# logique.net
KiCad netlist of a schematic drawn in Altium Designer
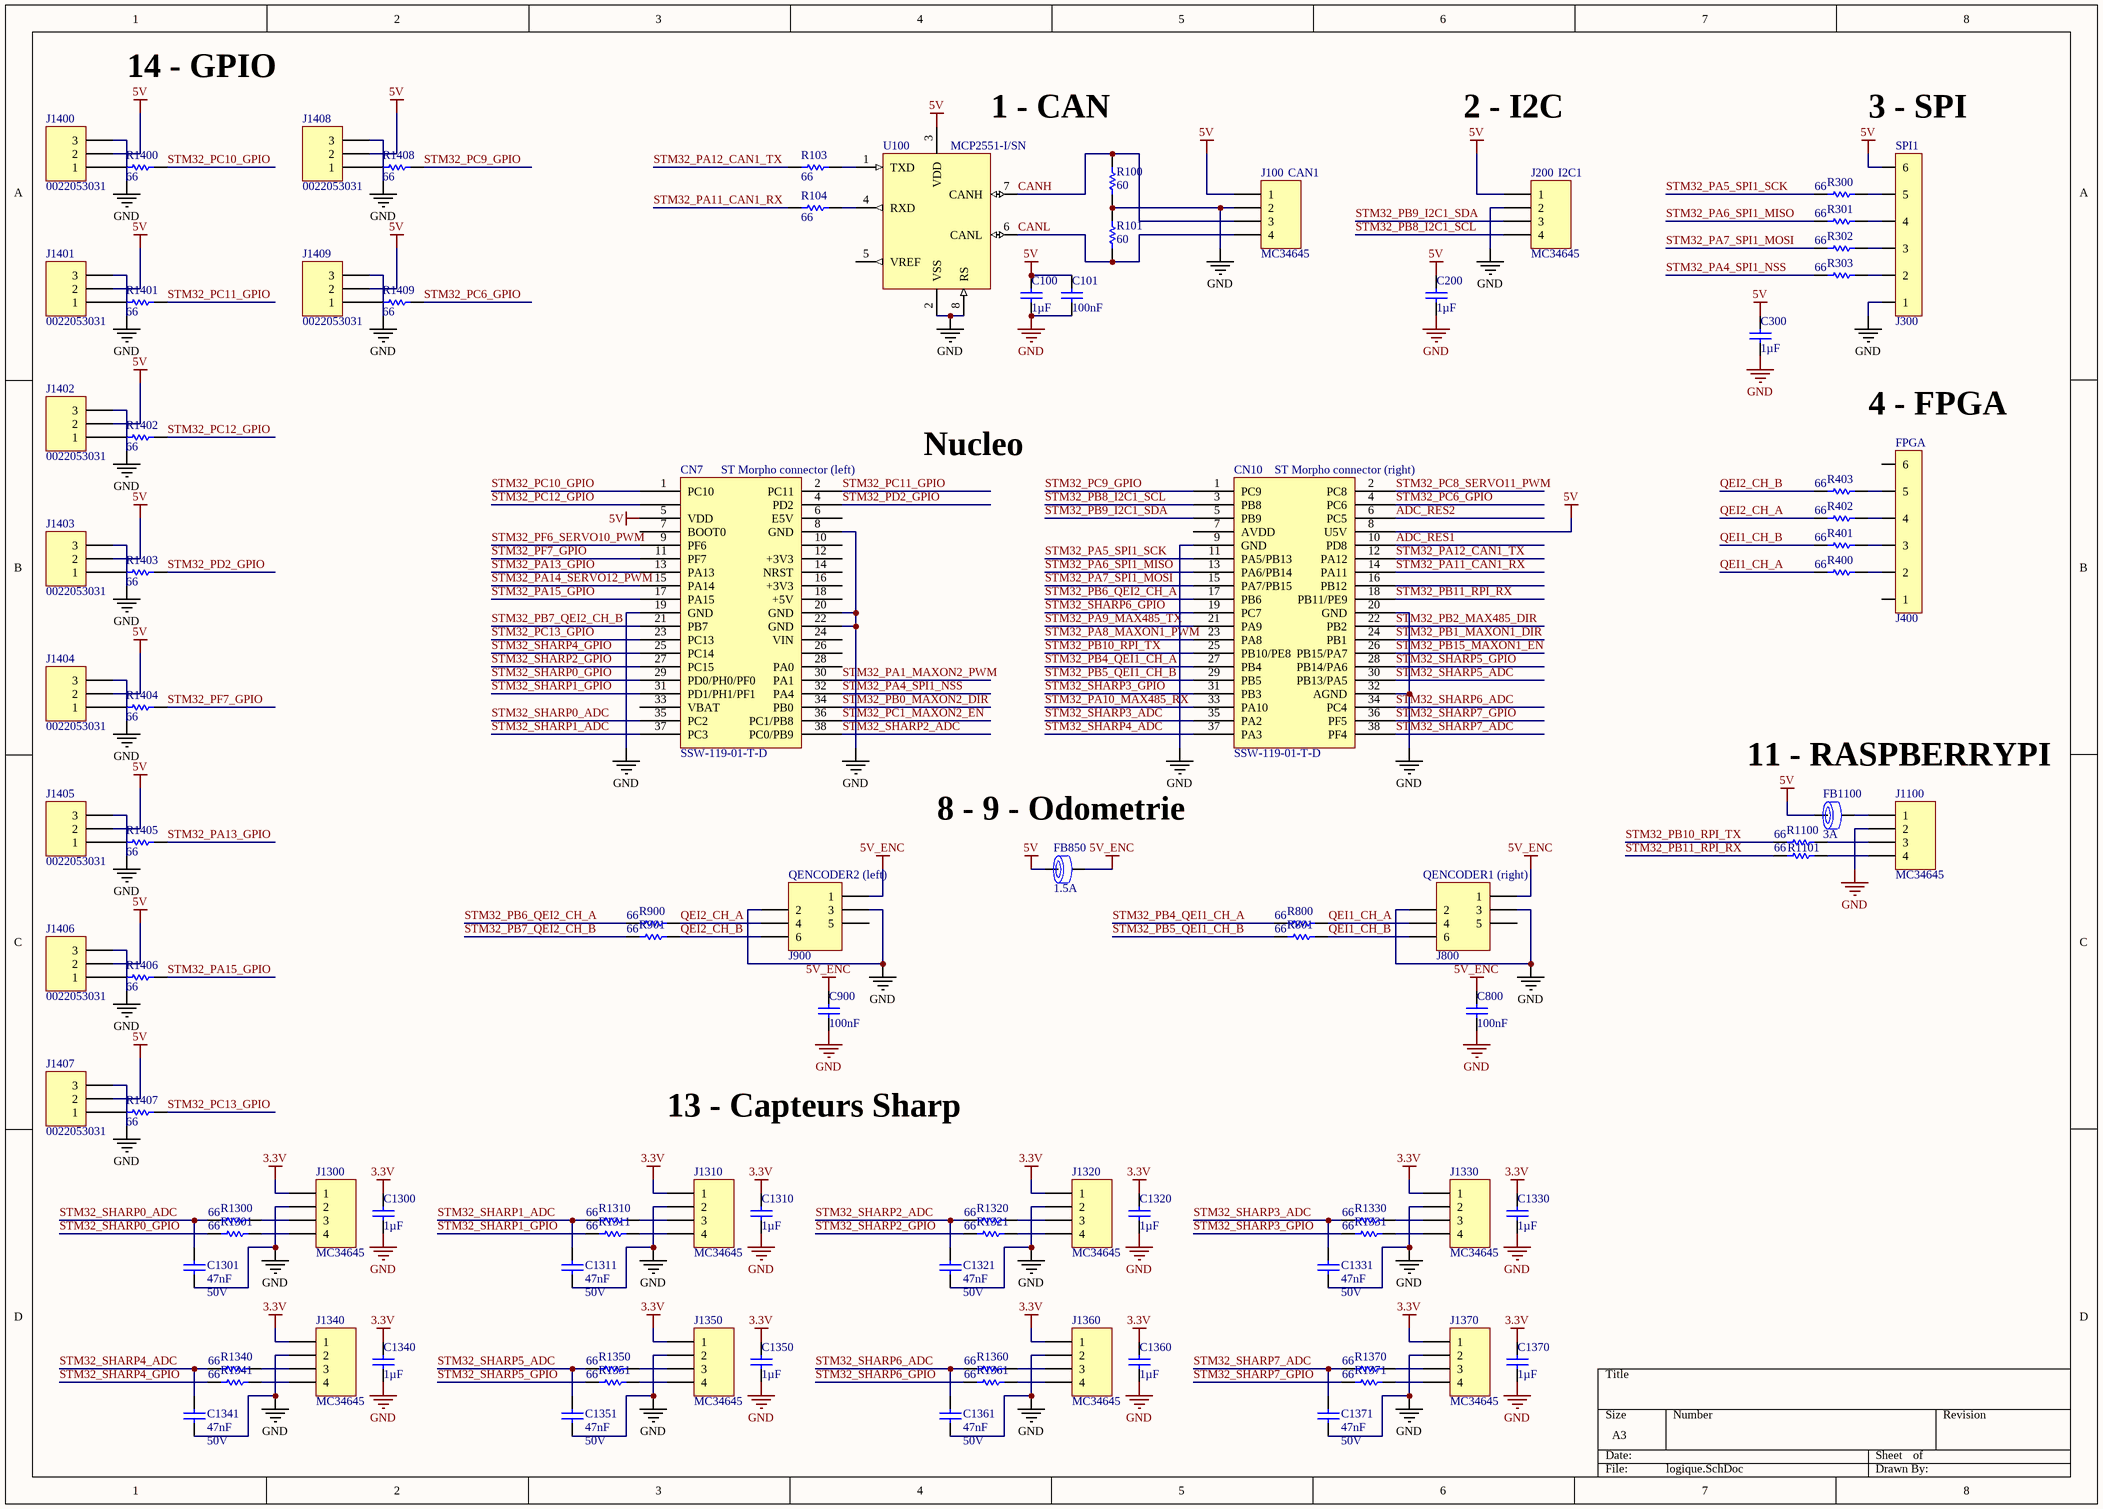
[diagram p0: logique.SchDoc]

(export (version "E")
  (design (tool "Eeschema 10.0.6"))
  (components
    (comp (ref "C100")
      (value "1µF")
      (footprint "C0805_N")
      (description "Capacitor")
      (fields (field (name "PUBLISHER") "Altium Limited"))
      (libsource (lib "_ROBOT") (part "Condensateur"))
    )
    (comp (ref "C101")
      (value "100nF")
      (footprint "C0805_N")
      (description "Capacitor")
      (fields (field (name "PUBLISHER") "Altium Limited"))
      (libsource (lib "_ROBOT") (part "Condensateur"))
    )
    (comp (ref "C200")
      (value "1µF")
      (footprint "C0805_N")
      (description "Capacitor")
      (fields (field (name "PUBLISHER") "Altium Limited"))
      (libsource (lib "_ROBOT") (part "Condensateur"))
    )
    (comp (ref "C300")
      (value "1µF")
      (footprint "C0805_N")
      (description "Capacitor")
      (fields (field (name "PUBLISHER") "Altium Limited"))
      (libsource (lib "_ROBOT") (part "Condensateur"))
    )
    (comp (ref "C800")
      (value "100nF")
      (footprint "C0805_N")
      (description "Capacitor")
      (fields (field (name "PUBLISHER") "Altium Limited"))
      (libsource (lib "_ROBOT") (part "Condensateur"))
    )
    (comp (ref "C900")
      (value "100nF")
      (footprint "C0805_N")
      (description "Capacitor")
      (fields (field (name "PUBLISHER") "Altium Limited"))
      (libsource (lib "_ROBOT") (part "Condensateur"))
    )
    (comp (ref "C1300")
      (value "1µF")
      (footprint "C0805_N")
      (description "Capacitor")
      (fields (field (name "PUBLISHER") "Altium Limited"))
      (libsource (lib "_ROBOT") (part "Condensateur"))
    )
    (comp (ref "C1301")
      (value "47nF")
      (footprint "WCAP-CSGP_0603, 1.6x0.8x0.8")
      (description "CAP CER 47nF 50V X7R 0603")
      (fields
        (field (name "MANUFACTURER") "Wurth Elektronik")
        (field (name "MANUFACTURER PART NUMBER") "885012206093")
        (field (name "RATEDVOLTAGE") "50V")
      )
      (libsource (lib "Condensateur") (part "WCAP-CSGP, 885012206093"))
    )
    (comp (ref "C1310")
      (value "1µF")
      (footprint "C0805_N")
      (description "Capacitor")
      (fields (field (name "PUBLISHER") "Altium Limited"))
      (libsource (lib "_ROBOT") (part "Condensateur"))
    )
    (comp (ref "C1311")
      (value "47nF")
      (footprint "WCAP-CSGP_0603, 1.6x0.8x0.8")
      (description "CAP CER 47nF 50V X7R 0603")
      (fields
        (field (name "MANUFACTURER") "Wurth Elektronik")
        (field (name "MANUFACTURER PART NUMBER") "885012206093")
        (field (name "RATEDVOLTAGE") "50V")
      )
      (libsource (lib "Condensateur") (part "WCAP-CSGP, 885012206093"))
    )
    (comp (ref "C1320")
      (value "1µF")
      (footprint "C0805_N")
      (description "Capacitor")
      (fields (field (name "PUBLISHER") "Altium Limited"))
      (libsource (lib "_ROBOT") (part "Condensateur"))
    )
    (comp (ref "C1321")
      (value "47nF")
      (footprint "WCAP-CSGP_0603, 1.6x0.8x0.8")
      (description "CAP CER 47nF 50V X7R 0603")
      (fields
        (field (name "MANUFACTURER") "Wurth Elektronik")
        (field (name "MANUFACTURER PART NUMBER") "885012206093")
        (field (name "RATEDVOLTAGE") "50V")
      )
      (libsource (lib "Condensateur") (part "WCAP-CSGP, 885012206093"))
    )
    (comp (ref "C1330")
      (value "1µF")
      (footprint "C0805_N")
      (description "Capacitor")
      (fields (field (name "PUBLISHER") "Altium Limited"))
      (libsource (lib "_ROBOT") (part "Condensateur"))
    )
    (comp (ref "C1331")
      (value "47nF")
      (footprint "WCAP-CSGP_0603, 1.6x0.8x0.8")
      (description "CAP CER 47nF 50V X7R 0603")
      (fields
        (field (name "MANUFACTURER") "Wurth Elektronik")
        (field (name "MANUFACTURER PART NUMBER") "885012206093")
        (field (name "RATEDVOLTAGE") "50V")
      )
      (libsource (lib "Condensateur") (part "WCAP-CSGP, 885012206093"))
    )
    (comp (ref "C1340")
      (value "1µF")
      (footprint "C0805_N")
      (description "Capacitor")
      (fields (field (name "PUBLISHER") "Altium Limited"))
      (libsource (lib "_ROBOT") (part "Condensateur"))
    )
    (comp (ref "C1341")
      (value "47nF")
      (footprint "WCAP-CSGP_0603, 1.6x0.8x0.8")
      (description "CAP CER 47nF 50V X7R 0603")
      (fields
        (field (name "MANUFACTURER") "Wurth Elektronik")
        (field (name "MANUFACTURER PART NUMBER") "885012206093")
        (field (name "RATEDVOLTAGE") "50V")
      )
      (libsource (lib "Condensateur") (part "WCAP-CSGP, 885012206093"))
    )
    (comp (ref "C1350")
      (value "1µF")
      (footprint "C0805_N")
      (description "Capacitor")
      (fields (field (name "PUBLISHER") "Altium Limited"))
      (libsource (lib "_ROBOT") (part "Condensateur"))
    )
    (comp (ref "C1351")
      (value "47nF")
      (footprint "WCAP-CSGP_0603, 1.6x0.8x0.8")
      (description "CAP CER 47nF 50V X7R 0603")
      (fields
        (field (name "MANUFACTURER") "Wurth Elektronik")
        (field (name "MANUFACTURER PART NUMBER") "885012206093")
        (field (name "RATEDVOLTAGE") "50V")
      )
      (libsource (lib "Condensateur") (part "WCAP-CSGP, 885012206093"))
    )
    (comp (ref "C1360")
      (value "1µF")
      (footprint "C0805_N")
      (description "Capacitor")
      (fields (field (name "PUBLISHER") "Altium Limited"))
      (libsource (lib "_ROBOT") (part "Condensateur"))
    )
    (comp (ref "C1361")
      (value "47nF")
      (footprint "WCAP-CSGP_0603, 1.6x0.8x0.8")
      (description "CAP CER 47nF 50V X7R 0603")
      (fields
        (field (name "MANUFACTURER") "Wurth Elektronik")
        (field (name "MANUFACTURER PART NUMBER") "885012206093")
        (field (name "RATEDVOLTAGE") "50V")
      )
      (libsource (lib "Condensateur") (part "WCAP-CSGP, 885012206093"))
    )
    (comp (ref "C1370")
      (value "1µF")
      (footprint "C0805_N")
      (description "Capacitor")
      (fields (field (name "PUBLISHER") "Altium Limited"))
      (libsource (lib "_ROBOT") (part "Condensateur"))
    )
    (comp (ref "C1371")
      (value "47nF")
      (footprint "WCAP-CSGP_0603, 1.6x0.8x0.8")
      (description "CAP CER 47nF 50V X7R 0603")
      (fields
        (field (name "MANUFACTURER") "Wurth Elektronik")
        (field (name "MANUFACTURER PART NUMBER") "885012206093")
        (field (name "RATEDVOLTAGE") "50V")
      )
      (libsource (lib "Condensateur") (part "WCAP-CSGP, 885012206093"))
    )
    (comp (ref "CN7")
      (value "SSW-119-01-T-D")
      (footprint "Samtec:CONN RCPT .100\" 38POS DUAL TIN")
      (description "CONN RCPT .100\" 38POS DUAL TIN")
      (fields (field (name "MANUFACTURER") "Samtec Inc."))
      (libsource (lib "Samtec") (part "SSW-119-01-T-D"))
    )
    (comp (ref "CN10")
      (value "SSW-119-01-T-D")
      (footprint "Samtec:CONN RCPT .100\" 38POS DUAL TIN")
      (description "CONN RCPT .100\" 38POS DUAL TIN")
      (fields (field (name "MANUFACTURER") "Samtec Inc."))
      (libsource (lib "Samtec") (part "SSW-119-01-T-D"))
    )
    (comp (ref "FB850")
      (value "742792624")
      (footprint "WE-CBF_0603_High Current")
      (description "Ferrite Bead 180ohm 0603 max1.5A")
      (fields (field (name "MANUFACTURER") "Wurth Elektronik") (field (name "RATEDCURRENT") "1.5A"))
      (libsource (lib "Inductance") (part "WE-CBF, 742792624"))
    )
    (comp (ref "FB1100")
      (value "742792023")
      (footprint "WE-CBF_0805_High Current")
      (description "Ferrite Bead 120ohm 0805 max3.0A")
      (fields (field (name "MANUFACTURER") "Wurth Elektronik") (field (name "RATEDCURRENT") "3A"))
      (libsource (lib "Inductance") (part "WE-CBF, 742792023"))
    )
    (comp (ref "J100")
      (value "MC34645")
      (footprint "HDR1X4")
      (description "MULTICOMP - MC34645 - EMB. MALE COUDEE  CON. MALE 2.54MM 4VOIE")
      (fields (field (name "MANUFACTURER") "MULTICOMP"))
      (libsource (lib "Divers") (part "MC34645"))
    )
    (comp (ref "J200")
      (value "MC34645")
      (footprint "HDR1X4")
      (description "MULTICOMP - MC34645 - EMB. MALE COUDEE  CON. MALE 2.54MM 4VOIE")
      (fields (field (name "MANUFACTURER") "MULTICOMP"))
      (libsource (lib "Divers") (part "MC34645"))
    )
    (comp (ref "J300")
      (value "22-03-2061")
      (footprint "22-03-2061")
      (libsource (lib "Connecteurs") (part "22-03-2061"))
    )
    (comp (ref "J400")
      (value "22-03-2061")
      (footprint "22-03-2061")
      (libsource (lib "Connecteurs") (part "22-03-2061"))
    )
    (comp (ref "J800")
      (value "~")
      (footprint "690367280676")
      (description "WR-MM Female SMT Connector with Polarization")
      (fields (field (name "MANUFACTURER PART NUMBER") "690367280676"))
      (libsource (lib "Connecteurs") (part "690367280676"))
    )
    (comp (ref "J900")
      (value "~")
      (footprint "690367280676")
      (description "WR-MM Female SMT Connector with Polarization")
      (fields (field (name "MANUFACTURER PART NUMBER") "690367280676"))
      (libsource (lib "Connecteurs") (part "690367280676"))
    )
    (comp (ref "J1100")
      (value "MC34645")
      (footprint "HDR1X4")
      (description "MULTICOMP - MC34645 - EMB. MALE COUDEE  CON. MALE 2.54MM 4VOIE")
      (fields (field (name "MANUFACTURER") "MULTICOMP"))
      (libsource (lib "Divers") (part "MC34645"))
    )
    (comp (ref "J1300")
      (value "MC34645")
      (footprint "HDR1X4")
      (description "MULTICOMP - MC34645 - EMB. MALE COUDEE  CON. MALE 2.54MM 4VOIE")
      (fields (field (name "MANUFACTURER") "MULTICOMP"))
      (libsource (lib "Connecteurs") (part "MC34645"))
    )
    (comp (ref "J1310")
      (value "MC34645")
      (footprint "HDR1X4")
      (description "MULTICOMP - MC34645 - EMB. MALE COUDEE  CON. MALE 2.54MM 4VOIE")
      (fields (field (name "MANUFACTURER") "MULTICOMP"))
      (libsource (lib "Connecteurs") (part "MC34645"))
    )
    (comp (ref "J1320")
      (value "MC34645")
      (footprint "HDR1X4")
      (description "MULTICOMP - MC34645 - EMB. MALE COUDEE  CON. MALE 2.54MM 4VOIE")
      (fields (field (name "MANUFACTURER") "MULTICOMP"))
      (libsource (lib "Connecteurs") (part "MC34645"))
    )
    (comp (ref "J1330")
      (value "MC34645")
      (footprint "HDR1X4")
      (description "MULTICOMP - MC34645 - EMB. MALE COUDEE  CON. MALE 2.54MM 4VOIE")
      (fields (field (name "MANUFACTURER") "MULTICOMP"))
      (libsource (lib "Connecteurs") (part "MC34645"))
    )
    (comp (ref "J1340")
      (value "MC34645")
      (footprint "HDR1X4")
      (description "MULTICOMP - MC34645 - EMB. MALE COUDEE  CON. MALE 2.54MM 4VOIE")
      (fields (field (name "MANUFACTURER") "MULTICOMP"))
      (libsource (lib "Connecteurs") (part "MC34645"))
    )
    (comp (ref "J1350")
      (value "MC34645")
      (footprint "HDR1X4")
      (description "MULTICOMP - MC34645 - EMB. MALE COUDEE  CON. MALE 2.54MM 4VOIE")
      (fields (field (name "MANUFACTURER") "MULTICOMP"))
      (libsource (lib "Connecteurs") (part "MC34645"))
    )
    (comp (ref "J1360")
      (value "MC34645")
      (footprint "HDR1X4")
      (description "MULTICOMP - MC34645 - EMB. MALE COUDEE  CON. MALE 2.54MM 4VOIE")
      (fields (field (name "MANUFACTURER") "MULTICOMP"))
      (libsource (lib "Connecteurs") (part "MC34645"))
    )
    (comp (ref "J1370")
      (value "MC34645")
      (footprint "HDR1X4")
      (description "MULTICOMP - MC34645 - EMB. MALE COUDEE  CON. MALE 2.54MM 4VOIE")
      (fields (field (name "MANUFACTURER") "MULTICOMP"))
      (libsource (lib "Connecteurs") (part "MC34645"))
    )
    (comp (ref "J1400")
      (value "0022053031")
      (footprint "HDR1X3")
      (description "CONN HEADER 3POS .100 R/A TIN")
      (fields (field (name "MANUFACTURER") "Molex, LLC"))
      (libsource (lib "Divers") (part "0022053031"))
    )
    (comp (ref "J1401")
      (value "0022053031")
      (footprint "HDR1X3")
      (description "CONN HEADER 3POS .100 R/A TIN")
      (fields (field (name "MANUFACTURER") "Molex, LLC"))
      (libsource (lib "Divers") (part "0022053031"))
    )
    (comp (ref "J1402")
      (value "0022053031")
      (footprint "HDR1X3")
      (description "CONN HEADER 3POS .100 R/A TIN")
      (fields (field (name "MANUFACTURER") "Molex, LLC"))
      (libsource (lib "Divers") (part "0022053031"))
    )
    (comp (ref "J1403")
      (value "0022053031")
      (footprint "HDR1X3")
      (description "CONN HEADER 3POS .100 R/A TIN")
      (fields (field (name "MANUFACTURER") "Molex, LLC"))
      (libsource (lib "Divers") (part "0022053031"))
    )
    (comp (ref "J1404")
      (value "0022053031")
      (footprint "HDR1X3")
      (description "CONN HEADER 3POS .100 R/A TIN")
      (fields (field (name "MANUFACTURER") "Molex, LLC"))
      (libsource (lib "Divers") (part "0022053031"))
    )
    (comp (ref "J1405")
      (value "0022053031")
      (footprint "HDR1X3")
      (description "CONN HEADER 3POS .100 R/A TIN")
      (fields (field (name "MANUFACTURER") "Molex, LLC"))
      (libsource (lib "Divers") (part "0022053031"))
    )
    (comp (ref "J1406")
      (value "0022053031")
      (footprint "HDR1X3")
      (description "CONN HEADER 3POS .100 R/A TIN")
      (fields (field (name "MANUFACTURER") "Molex, LLC"))
      (libsource (lib "Divers") (part "0022053031"))
    )
    (comp (ref "J1407")
      (value "0022053031")
      (footprint "HDR1X3")
      (description "CONN HEADER 3POS .100 R/A TIN")
      (fields (field (name "MANUFACTURER") "Molex, LLC"))
      (libsource (lib "Divers") (part "0022053031"))
    )
    (comp (ref "J1408")
      (value "0022053031")
      (footprint "HDR1X3")
      (description "CONN HEADER 3POS .100 R/A TIN")
      (fields (field (name "MANUFACTURER") "Molex, LLC"))
      (libsource (lib "Divers") (part "0022053031"))
    )
    (comp (ref "J1409")
      (value "0022053031")
      (footprint "HDR1X3")
      (description "CONN HEADER 3POS .100 R/A TIN")
      (fields (field (name "MANUFACTURER") "Molex, LLC"))
      (libsource (lib "Divers") (part "0022053031"))
    )
    (comp (ref "R100")
      (value "60")
      (footprint "R0805_N")
      (description "Resistor")
      (fields (field (name "PUBLISHER") "Altium Limited"))
      (libsource (lib "_ROBOT") (part "Resistor"))
    )
    (comp (ref "R101")
      (value "60")
      (footprint "R0805_N")
      (description "Resistor")
      (fields (field (name "PUBLISHER") "Altium Limited"))
      (libsource (lib "_ROBOT") (part "Resistor"))
    )
    (comp (ref "R103")
      (value "66")
      (footprint "R0805_N")
      (description "Resistor")
      (fields (field (name "PUBLISHER") "Altium Limited"))
      (libsource (lib "_ROBOT") (part "Resistor"))
    )
    (comp (ref "R104")
      (value "66")
      (footprint "R0805_N")
      (description "Resistor")
      (fields (field (name "PUBLISHER") "Altium Limited"))
      (libsource (lib "_ROBOT") (part "Resistor"))
    )
    (comp (ref "R300")
      (value "66")
      (footprint "R0805_N")
      (description "Resistor")
      (fields (field (name "PUBLISHER") "Altium Limited"))
      (libsource (lib "_ROBOT") (part "Resistor"))
    )
    (comp (ref "R301")
      (value "66")
      (footprint "R0805_N")
      (description "Resistor")
      (fields (field (name "PUBLISHER") "Altium Limited"))
      (libsource (lib "_ROBOT") (part "Resistor"))
    )
    (comp (ref "R302")
      (value "66")
      (footprint "R0805_N")
      (description "Resistor")
      (fields (field (name "PUBLISHER") "Altium Limited"))
      (libsource (lib "_ROBOT") (part "Resistor"))
    )
    (comp (ref "R303")
      (value "66")
      (footprint "R0805_N")
      (description "Resistor")
      (fields (field (name "PUBLISHER") "Altium Limited"))
      (libsource (lib "_ROBOT") (part "Resistor"))
    )
    (comp (ref "R400")
      (value "66")
      (footprint "R0805_N")
      (description "Resistor")
      (fields (field (name "PUBLISHER") "Altium Limited"))
      (libsource (lib "_ROBOT") (part "Resistor"))
    )
    (comp (ref "R401")
      (value "66")
      (footprint "R0805_N")
      (description "Resistor")
      (fields (field (name "PUBLISHER") "Altium Limited"))
      (libsource (lib "_ROBOT") (part "Resistor"))
    )
    (comp (ref "R402")
      (value "66")
      (footprint "R0805_N")
      (description "Resistor")
      (fields (field (name "PUBLISHER") "Altium Limited"))
      (libsource (lib "_ROBOT") (part "Resistor"))
    )
    (comp (ref "R403")
      (value "66")
      (footprint "R0805_N")
      (description "Resistor")
      (fields (field (name "PUBLISHER") "Altium Limited"))
      (libsource (lib "_ROBOT") (part "Resistor"))
    )
    (comp (ref "R800")
      (value "66")
      (footprint "R0805_N")
      (description "Resistor")
      (fields (field (name "PUBLISHER") "Altium Limited"))
      (libsource (lib "_ROBOT") (part "Resistor"))
    )
    (comp (ref "R801")
      (value "66")
      (footprint "R0805_N")
      (description "Resistor")
      (fields (field (name "PUBLISHER") "Altium Limited"))
      (libsource (lib "_ROBOT") (part "Resistor"))
    )
    (comp (ref "R900")
      (value "66")
      (footprint "R0805_N")
      (description "Resistor")
      (fields (field (name "PUBLISHER") "Altium Limited"))
      (libsource (lib "_ROBOT") (part "Resistor"))
    )
    (comp (ref "R901")
      (value "66")
      (footprint "R0805_N")
      (description "Resistor")
      (fields (field (name "PUBLISHER") "Altium Limited"))
      (libsource (lib "_ROBOT") (part "Resistor"))
    )
    (comp (ref "R1100")
      (value "66")
      (footprint "R0805_N")
      (description "Resistor")
      (fields (field (name "PUBLISHER") "Altium Limited"))
      (libsource (lib "_ROBOT") (part "Resistor"))
    )
    (comp (ref "R1101")
      (value "66")
      (footprint "R0805_N")
      (description "Resistor")
      (fields (field (name "PUBLISHER") "Altium Limited"))
      (libsource (lib "_ROBOT") (part "Resistor"))
    )
    (comp (ref "R1300")
      (value "66")
      (footprint "R0805_N")
      (description "Resistor")
      (fields (field (name "PUBLISHER") "Altium Limited"))
      (libsource (lib "_ROBOT") (part "Resistor"))
    )
    (comp (ref "R1301")
      (value "66")
      (footprint "R0805_N")
      (description "Resistor")
      (fields (field (name "PUBLISHER") "Altium Limited"))
      (libsource (lib "_ROBOT") (part "Resistor"))
    )
    (comp (ref "R1310")
      (value "66")
      (footprint "R0805_N")
      (description "Resistor")
      (fields (field (name "PUBLISHER") "Altium Limited"))
      (libsource (lib "_ROBOT") (part "Resistor"))
    )
    (comp (ref "R1311")
      (value "66")
      (footprint "R0805_N")
      (description "Resistor")
      (fields (field (name "PUBLISHER") "Altium Limited"))
      (libsource (lib "_ROBOT") (part "Resistor"))
    )
    (comp (ref "R1320")
      (value "66")
      (footprint "R0805_N")
      (description "Resistor")
      (fields (field (name "PUBLISHER") "Altium Limited"))
      (libsource (lib "_ROBOT") (part "Resistor"))
    )
    (comp (ref "R1321")
      (value "66")
      (footprint "R0805_N")
      (description "Resistor")
      (fields (field (name "PUBLISHER") "Altium Limited"))
      (libsource (lib "_ROBOT") (part "Resistor"))
    )
    (comp (ref "R1330")
      (value "66")
      (footprint "R0805_N")
      (description "Resistor")
      (fields (field (name "PUBLISHER") "Altium Limited"))
      (libsource (lib "_ROBOT") (part "Resistor"))
    )
    (comp (ref "R1331")
      (value "66")
      (footprint "R0805_N")
      (description "Resistor")
      (fields (field (name "PUBLISHER") "Altium Limited"))
      (libsource (lib "_ROBOT") (part "Resistor"))
    )
    (comp (ref "R1340")
      (value "66")
      (footprint "R0805_N")
      (description "Resistor")
      (fields (field (name "PUBLISHER") "Altium Limited"))
      (libsource (lib "_ROBOT") (part "Resistor"))
    )
    (comp (ref "R1341")
      (value "66")
      (footprint "R0805_N")
      (description "Resistor")
      (fields (field (name "PUBLISHER") "Altium Limited"))
      (libsource (lib "_ROBOT") (part "Resistor"))
    )
    (comp (ref "R1350")
      (value "66")
      (footprint "R0805_N")
      (description "Resistor")
      (fields (field (name "PUBLISHER") "Altium Limited"))
      (libsource (lib "_ROBOT") (part "Resistor"))
    )
    (comp (ref "R1351")
      (value "66")
      (footprint "R0805_N")
      (description "Resistor")
      (fields (field (name "PUBLISHER") "Altium Limited"))
      (libsource (lib "_ROBOT") (part "Resistor"))
    )
    (comp (ref "R1360")
      (value "66")
      (footprint "R0805_N")
      (description "Resistor")
      (fields (field (name "PUBLISHER") "Altium Limited"))
      (libsource (lib "_ROBOT") (part "Resistor"))
    )
    (comp (ref "R1361")
      (value "66")
      (footprint "R0805_N")
      (description "Resistor")
      (fields (field (name "PUBLISHER") "Altium Limited"))
      (libsource (lib "_ROBOT") (part "Resistor"))
    )
    (comp (ref "R1370")
      (value "66")
      (footprint "R0805_N")
      (description "Resistor")
      (fields (field (name "PUBLISHER") "Altium Limited"))
      (libsource (lib "_ROBOT") (part "Resistor"))
    )
    (comp (ref "R1371")
      (value "66")
      (footprint "R0805_N")
      (description "Resistor")
      (fields (field (name "PUBLISHER") "Altium Limited"))
      (libsource (lib "_ROBOT") (part "Resistor"))
    )
    (comp (ref "R1400")
      (value "66")
      (footprint "R0805_N")
      (description "Resistor")
      (fields (field (name "PUBLISHER") "Altium Limited"))
      (libsource (lib "_ROBOT") (part "Resistor"))
    )
    (comp (ref "R1401")
      (value "66")
      (footprint "R0805_N")
      (description "Resistor")
      (fields (field (name "PUBLISHER") "Altium Limited"))
      (libsource (lib "_ROBOT") (part "Resistor"))
    )
    (comp (ref "R1402")
      (value "66")
      (footprint "R0805_N")
      (description "Resistor")
      (fields (field (name "PUBLISHER") "Altium Limited"))
      (libsource (lib "_ROBOT") (part "Resistor"))
    )
    (comp (ref "R1403")
      (value "66")
      (footprint "R0805_N")
      (description "Resistor")
      (fields (field (name "PUBLISHER") "Altium Limited"))
      (libsource (lib "_ROBOT") (part "Resistor"))
    )
    (comp (ref "R1404")
      (value "66")
      (footprint "R0805_N")
      (description "Resistor")
      (fields (field (name "PUBLISHER") "Altium Limited"))
      (libsource (lib "_ROBOT") (part "Resistor"))
    )
    (comp (ref "R1405")
      (value "66")
      (footprint "R0805_N")
      (description "Resistor")
      (fields (field (name "PUBLISHER") "Altium Limited"))
      (libsource (lib "_ROBOT") (part "Resistor"))
    )
    (comp (ref "R1406")
      (value "66")
      (footprint "R0805_N")
      (description "Resistor")
      (fields (field (name "PUBLISHER") "Altium Limited"))
      (libsource (lib "_ROBOT") (part "Resistor"))
    )
    (comp (ref "R1407")
      (value "66")
      (footprint "R0805_N")
      (description "Resistor")
      (fields (field (name "PUBLISHER") "Altium Limited"))
      (libsource (lib "_ROBOT") (part "Resistor"))
    )
    (comp (ref "R1408")
      (value "66")
      (footprint "R0805_N")
      (description "Resistor")
      (fields (field (name "PUBLISHER") "Altium Limited"))
      (libsource (lib "_ROBOT") (part "Resistor"))
    )
    (comp (ref "R1409")
      (value "66")
      (footprint "R0805_N")
      (description "Resistor")
      (fields (field (name "PUBLISHER") "Altium Limited"))
      (libsource (lib "_ROBOT") (part "Resistor"))
    )
    (comp (ref "U100")
      (value "MCP2551-I/SN")
      (footprint "SO8_N")
      (description "IC TRANSCEIVER CAN HI-SPD 8-SOIC")
      (fields (field (name "MANUFACTURER") "Microchip Technology"))
      (libsource (lib "Serial") (part "MCP2551-I/SN"))
    )
  )
  (nets
    (net (code "1") (name "/ADC_RES1") (class "Default") (node (ref "CN10") (pin "10") (pintype "passive")))
    (net (code "2") (name "/ADC_RES2") (class "Default")
      (node (ref "CN10") (pin "6") (pinfunction "E5V_6") (pintype "passive"))
    )
    (net (code "3") (name "/CANH") (class "Default")
      (node (ref "J100") (pin "3") (pinfunction "3_3") (pintype "passive"))
      (node (ref "R100") (pin "2") (pinfunction "2_2") (pintype "passive"))
      (node (ref "U100") (pin "7") (pinfunction "CANH_7") (pintype "bidirectional"))
    )
    (net (code "4") (name "/CANL") (class "Default")
      (node (ref "J100") (pin "4") (pinfunction "4_4") (pintype "passive"))
      (node (ref "R101") (pin "1") (pinfunction "1_1") (pintype "passive"))
      (node (ref "U100") (pin "6") (pinfunction "CANL_6") (pintype "bidirectional"))
    )
    (net (code "5") (name "/QEI1_CH_A") (class "Default")
      (node (ref "J800") (pin "4") (pinfunction "4_4") (pintype "passive"))
      (node (ref "R400") (pin "2") (pinfunction "2_2") (pintype "passive"))
      (node (ref "R800") (pin "1") (pinfunction "1_1") (pintype "passive"))
    )
    (net (code "6") (name "/QEI1_CH_B") (class "Default")
      (node (ref "J800") (pin "6") (pinfunction "6_6") (pintype "passive"))
      (node (ref "R401") (pin "2") (pinfunction "2_2") (pintype "passive"))
      (node (ref "R801") (pin "1") (pinfunction "1_1") (pintype "passive"))
    )
    (net (code "7") (name "/QEI2_CH_A") (class "Default")
      (node (ref "J900") (pin "4") (pinfunction "4_4") (pintype "passive"))
      (node (ref "R402") (pin "2") (pinfunction "2_2") (pintype "passive"))
      (node (ref "R900") (pin "1") (pinfunction "1_1") (pintype "passive"))
    )
    (net (code "8") (name "/QEI2_CH_B") (class "Default")
      (node (ref "J900") (pin "6") (pinfunction "6_6") (pintype "passive"))
      (node (ref "R403") (pin "2") (pinfunction "2_2") (pintype "passive"))
      (node (ref "R901") (pin "1") (pinfunction "1_1") (pintype "passive"))
    )
    (net (code "9") (name "/STM32_PA1_MAXON2_PWM") (class "Default")
      (node (ref "CN7") (pin "30") (pinfunction "PA1_30") (pintype "passive"))
    )
    (net (code "10") (name "/STM32_PA4_SPI1_NSS") (class "Default")
      (node (ref "CN7") (pin "32") (pinfunction "PA4_32") (pintype "passive"))
      (node (ref "R303") (pin "2") (pinfunction "2_2") (pintype "passive"))
    )
    (net (code "11") (name "/STM32_PA5_SPI1_SCK") (class "Default")
      (node (ref "CN10") (pin "11") (pinfunction "PF7_11") (pintype "passive"))
      (node (ref "R300") (pin "2") (pinfunction "2_2") (pintype "passive"))
    )
    (net (code "12") (name "/STM32_PA6_SPI1_MISO") (class "Default")
      (node (ref "CN10") (pin "13") (pinfunction "PA13_13") (pintype "passive"))
      (node (ref "R301") (pin "2") (pinfunction "2_2") (pintype "passive"))
    )
    (net (code "13") (name "/STM32_PA7_SPI1_MOSI") (class "Default")
      (node (ref "CN10") (pin "15") (pinfunction "PA14_15") (pintype "passive"))
      (node (ref "R302") (pin "2") (pinfunction "2_2") (pintype "passive"))
    )
    (net (code "14") (name "/STM32_PA8_MAXON1_PWM") (class "Default")
      (node (ref "CN10") (pin "23") (pinfunction "PC13_23") (pintype "passive"))
    )
    (net (code "15") (name "/STM32_PA9_MAX485_TX") (class "Default")
      (node (ref "CN10") (pin "21") (pinfunction "PB7_21") (pintype "passive"))
    )
    (net (code "16") (name "/STM32_PA10_MAX485_RX") (class "Default")
      (node (ref "CN10") (pin "33") (pinfunction "VBAT_33") (pintype "passive"))
    )
    (net (code "17") (name "/STM32_PA11_CAN1_RX") (class "Default")
      (node (ref "CN10") (pin "14") (pinfunction "NRST_14") (pintype "passive"))
      (node (ref "R104") (pin "2") (pinfunction "2_2") (pintype "passive"))
    )
    (net (code "18") (name "/STM32_PA12_CAN1_TX") (class "Default")
      (node (ref "CN10") (pin "12") (pinfunction "+3V3_12") (pintype "passive"))
      (node (ref "R103") (pin "2") (pinfunction "2_2") (pintype "passive"))
    )
    (net (code "19") (name "/STM32_PA13_GPIO") (class "Default")
      (node (ref "CN7") (pin "13") (pinfunction "PA13_13") (pintype "passive"))
      (node (ref "R1405") (pin "1") (pinfunction "1_1") (pintype "passive"))
    )
    (net (code "20") (name "/STM32_PA14_SERVO12_PWM") (class "Default")
      (node (ref "CN7") (pin "15") (pinfunction "PA14_15") (pintype "passive"))
    )
    (net (code "21") (name "/STM32_PA15_GPIO") (class "Default")
      (node (ref "CN7") (pin "17") (pinfunction "PA15_17") (pintype "passive"))
      (node (ref "R1406") (pin "1") (pinfunction "1_1") (pintype "passive"))
    )
    (net (code "22") (name "/STM32_PB0_MAXON2_DIR") (class "Default")
      (node (ref "CN7") (pin "34") (pinfunction "PB0_34") (pintype "passive"))
    )
    (net (code "23") (name "/STM32_PB1_MAXON1_DIR") (class "Default")
      (node (ref "CN10") (pin "24") (pinfunction "VIN_24") (pintype "passive"))
    )
    (net (code "24") (name "/STM32_PB2_MAX485_DIR") (class "Default")
      (node (ref "CN10") (pin "22") (pinfunction "GND_22") (pintype "passive"))
    )
    (net (code "25") (name "/STM32_PB4_QEI1_CH_A") (class "Default")
      (node (ref "CN10") (pin "27") (pinfunction "PC15_27") (pintype "passive"))
      (node (ref "R800") (pin "2") (pinfunction "2_2") (pintype "passive"))
    )
    (net (code "26") (name "/STM32_PB5_QEI1_CH_B") (class "Default")
      (node (ref "CN10") (pin "29") (pinfunction "PD0/PH0/PF0_29") (pintype "passive"))
      (node (ref "R801") (pin "2") (pinfunction "2_2") (pintype "passive"))
    )
    (net (code "27") (name "/STM32_PB6_QEI2_CH_A") (class "Default")
      (node (ref "CN10") (pin "17") (pinfunction "PA15_17") (pintype "passive"))
      (node (ref "R900") (pin "2") (pinfunction "2_2") (pintype "passive"))
    )
    (net (code "28") (name "/STM32_PB7_QEI2_CH_B") (class "Default")
      (node (ref "CN7") (pin "21") (pinfunction "PB7_21") (pintype "passive"))
      (node (ref "R901") (pin "2") (pinfunction "2_2") (pintype "passive"))
    )
    (net (code "29") (name "/STM32_PB8_I2C1_SCL") (class "Default")
      (node (ref "CN10") (pin "3") (pinfunction "PC12_3") (pintype "passive"))
      (node (ref "J200") (pin "4") (pinfunction "4_4") (pintype "passive"))
    )
    (net (code "30") (name "/STM32_PB9_I2C1_SDA") (class "Default")
      (node (ref "CN10") (pin "5") (pinfunction "VDD_5") (pintype "passive"))
      (node (ref "J200") (pin "3") (pinfunction "3_3") (pintype "passive"))
    )
    (net (code "31") (name "/STM32_PB10_RPI_TX") (class "Default")
      (node (ref "CN10") (pin "25") (pinfunction "PC14_25") (pintype "passive"))
      (node (ref "R1100") (pin "2") (pinfunction "2_2") (pintype "passive"))
    )
    (net (code "32") (name "/STM32_PB11_RPI_RX") (class "Default")
      (node (ref "CN10") (pin "18") (pinfunction "+5V_18") (pintype "passive"))
      (node (ref "R1101") (pin "2") (pinfunction "2_2") (pintype "passive"))
    )
    (net (code "33") (name "/STM32_PB15_MAXON1_EN") (class "Default")
      (node (ref "CN10") (pin "26") (pintype "passive"))
    )
    (net (code "34") (name "/STM32_PC1_MAXON2_EN") (class "Default")
      (node (ref "CN7") (pin "36") (pinfunction "PC1/PB8_36") (pintype "passive"))
    )
    (net (code "35") (name "/STM32_PC6_GPIO") (class "Default")
      (node (ref "CN10") (pin "4") (pinfunction "PD2_4") (pintype "passive"))
      (node (ref "R1409") (pin "1") (pinfunction "1_1") (pintype "passive"))
    )
    (net (code "36") (name "/STM32_PC8_SERVO11_PWM") (class "Default")
      (node (ref "CN10") (pin "2") (pinfunction "PC11_2") (pintype "passive"))
    )
    (net (code "37") (name "/STM32_PC9_GPIO") (class "Default")
      (node (ref "CN10") (pin "1") (pinfunction "PC10_1") (pintype "passive"))
      (node (ref "R1408") (pin "1") (pinfunction "1_1") (pintype "passive"))
    )
    (net (code "38") (name "/STM32_PC10_GPIO") (class "Default")
      (node (ref "CN7") (pin "1") (pinfunction "PC10_1") (pintype "passive"))
      (node (ref "R1400") (pin "1") (pinfunction "1_1") (pintype "passive"))
    )
    (net (code "39") (name "/STM32_PC11_GPIO") (class "Default")
      (node (ref "CN7") (pin "2") (pinfunction "PC11_2") (pintype "passive"))
      (node (ref "R1401") (pin "1") (pinfunction "1_1") (pintype "passive"))
    )
    (net (code "40") (name "/STM32_PC12_GPIO") (class "Default")
      (node (ref "CN7") (pin "3") (pinfunction "PC12_3") (pintype "passive"))
      (node (ref "R1402") (pin "1") (pinfunction "1_1") (pintype "passive"))
    )
    (net (code "41") (name "/STM32_PC13_GPIO") (class "Default")
      (node (ref "CN7") (pin "23") (pinfunction "PC13_23") (pintype "passive"))
      (node (ref "R1407") (pin "1") (pinfunction "1_1") (pintype "passive"))
    )
    (net (code "42") (name "/STM32_PD2_GPIO") (class "Default")
      (node (ref "CN7") (pin "4") (pinfunction "PD2_4") (pintype "passive"))
      (node (ref "R1403") (pin "1") (pinfunction "1_1") (pintype "passive"))
    )
    (net (code "43") (name "/STM32_PF6_SERVO10_PWM") (class "Default")
      (node (ref "CN7") (pin "9") (pinfunction "PF6_9") (pintype "passive"))
    )
    (net (code "44") (name "/STM32_PF7_GPIO") (class "Default")
      (node (ref "CN7") (pin "11") (pinfunction "PF7_11") (pintype "passive"))
      (node (ref "R1404") (pin "1") (pinfunction "1_1") (pintype "passive"))
    )
    (net (code "45") (name "/STM32_SHARP0_ADC") (class "Default")
      (node (ref "C1301") (pin "2") (pinfunction "2_2") (pintype "passive"))
      (node (ref "CN7") (pin "35") (pinfunction "PC2_35") (pintype "passive"))
      (node (ref "R1300") (pin "2") (pinfunction "2_2") (pintype "passive"))
    )
    (net (code "46") (name "/STM32_SHARP0_GPIO") (class "Default")
      (node (ref "CN7") (pin "29") (pinfunction "PD0/PH0/PF0_29") (pintype "passive"))
      (node (ref "R1301") (pin "2") (pinfunction "2_2") (pintype "passive"))
    )
    (net (code "47") (name "/STM32_SHARP1_ADC") (class "Default")
      (node (ref "C1311") (pin "2") (pinfunction "2_2") (pintype "passive"))
      (node (ref "CN7") (pin "37") (pinfunction "PC3_37") (pintype "passive"))
      (node (ref "R1310") (pin "2") (pinfunction "2_2") (pintype "passive"))
    )
    (net (code "48") (name "/STM32_SHARP1_GPIO") (class "Default")
      (node (ref "CN7") (pin "31") (pinfunction "PD1/PH1/PF1_31") (pintype "passive"))
      (node (ref "R1311") (pin "2") (pinfunction "2_2") (pintype "passive"))
    )
    (net (code "49") (name "/STM32_SHARP2_ADC") (class "Default")
      (node (ref "C1321") (pin "2") (pinfunction "2_2") (pintype "passive"))
      (node (ref "CN7") (pin "38") (pinfunction "PC0/PB9_38") (pintype "passive"))
      (node (ref "R1320") (pin "2") (pinfunction "2_2") (pintype "passive"))
    )
    (net (code "50") (name "/STM32_SHARP2_GPIO") (class "Default")
      (node (ref "CN7") (pin "27") (pinfunction "PC15_27") (pintype "passive"))
      (node (ref "R1321") (pin "2") (pinfunction "2_2") (pintype "passive"))
    )
    (net (code "51") (name "/STM32_SHARP3_ADC") (class "Default")
      (node (ref "C1331") (pin "2") (pinfunction "2_2") (pintype "passive"))
      (node (ref "CN10") (pin "35") (pinfunction "PC2_35") (pintype "passive"))
      (node (ref "R1330") (pin "2") (pinfunction "2_2") (pintype "passive"))
    )
    (net (code "52") (name "/STM32_SHARP3_GPIO") (class "Default")
      (node (ref "CN10") (pin "31") (pinfunction "PD1/PH1/PF1_31") (pintype "passive"))
      (node (ref "R1331") (pin "2") (pinfunction "2_2") (pintype "passive"))
    )
    (net (code "53") (name "/STM32_SHARP4_ADC") (class "Default")
      (node (ref "C1341") (pin "2") (pinfunction "2_2") (pintype "passive"))
      (node (ref "CN10") (pin "37") (pinfunction "PC3_37") (pintype "passive"))
      (node (ref "R1340") (pin "2") (pinfunction "2_2") (pintype "passive"))
    )
    (net (code "54") (name "/STM32_SHARP4_GPIO") (class "Default")
      (node (ref "CN7") (pin "25") (pinfunction "PC14_25") (pintype "passive"))
      (node (ref "R1341") (pin "2") (pinfunction "2_2") (pintype "passive"))
    )
    (net (code "55") (name "/STM32_SHARP5_ADC") (class "Default")
      (node (ref "C1351") (pin "2") (pinfunction "2_2") (pintype "passive"))
      (node (ref "CN10") (pin "30") (pinfunction "PA1_30") (pintype "passive"))
      (node (ref "R1350") (pin "2") (pinfunction "2_2") (pintype "passive"))
    )
    (net (code "56") (name "/STM32_SHARP5_GPIO") (class "Default")
      (node (ref "CN10") (pin "28") (pinfunction "PA0_28") (pintype "passive"))
      (node (ref "R1351") (pin "2") (pinfunction "2_2") (pintype "passive"))
    )
    (net (code "57") (name "/STM32_SHARP6_ADC") (class "Default")
      (node (ref "C1361") (pin "2") (pinfunction "2_2") (pintype "passive"))
      (node (ref "CN10") (pin "34") (pinfunction "PB0_34") (pintype "passive"))
      (node (ref "R1360") (pin "2") (pinfunction "2_2") (pintype "passive"))
    )
    (net (code "58") (name "/STM32_SHARP6_GPIO") (class "Default")
      (node (ref "CN10") (pin "19") (pinfunction "GND_19") (pintype "passive"))
      (node (ref "R1361") (pin "2") (pinfunction "2_2") (pintype "passive"))
    )
    (net (code "59") (name "/STM32_SHARP7_ADC") (class "Default")
      (node (ref "C1371") (pin "2") (pinfunction "2_2") (pintype "passive"))
      (node (ref "CN10") (pin "38") (pinfunction "PC0/PB9_38") (pintype "passive"))
      (node (ref "R1370") (pin "2") (pinfunction "2_2") (pintype "passive"))
    )
    (net (code "60") (name "/STM32_SHARP7_GPIO") (class "Default")
      (node (ref "CN10") (pin "36") (pinfunction "PC1/PB8_36") (pintype "passive"))
      (node (ref "R1371") (pin "2") (pinfunction "2_2") (pintype "passive"))
    )
    (net (code "61") (name "3.3V") (class "Default")
      (node (ref "C1300") (pin "2") (pinfunction "2_2") (pintype "passive"))
      (node (ref "C1310") (pin "2") (pinfunction "2_2") (pintype "passive"))
      (node (ref "C1320") (pin "2") (pinfunction "2_2") (pintype "passive"))
      (node (ref "C1330") (pin "2") (pinfunction "2_2") (pintype "passive"))
      (node (ref "C1340") (pin "2") (pinfunction "2_2") (pintype "passive"))
      (node (ref "C1350") (pin "2") (pinfunction "2_2") (pintype "passive"))
      (node (ref "C1360") (pin "2") (pinfunction "2_2") (pintype "passive"))
      (node (ref "C1370") (pin "2") (pinfunction "2_2") (pintype "passive"))
      (node (ref "J1300") (pin "1") (pinfunction "1_1") (pintype "passive"))
      (node (ref "J1310") (pin "1") (pinfunction "1_1") (pintype "passive"))
      (node (ref "J1320") (pin "1") (pinfunction "1_1") (pintype "passive"))
      (node (ref "J1330") (pin "1") (pinfunction "1_1") (pintype "passive"))
      (node (ref "J1340") (pin "1") (pinfunction "1_1") (pintype "passive"))
      (node (ref "J1350") (pin "1") (pinfunction "1_1") (pintype "passive"))
      (node (ref "J1360") (pin "1") (pinfunction "1_1") (pintype "passive"))
      (node (ref "J1370") (pin "1") (pinfunction "1_1") (pintype "passive"))
    )
    (net (code "62") (name "5V") (class "Default")
      (node (ref "C100") (pin "2") (pinfunction "2_2") (pintype "passive"))
      (node (ref "C101") (pin "2") (pinfunction "2_2") (pintype "passive"))
      (node (ref "C200") (pin "2") (pinfunction "2_2") (pintype "passive"))
      (node (ref "C300") (pin "2") (pinfunction "2_2") (pintype "passive"))
      (node (ref "CN10") (pin "8") (pinfunction "GND_8") (pintype "passive"))
      (node (ref "CN7") (pin "5") (pinfunction "VDD_5") (pintype "passive"))
      (node (ref "FB1100") (pin "1") (pinfunction "1_1") (pintype "passive"))
      (node (ref "FB850") (pin "1") (pinfunction "1_1") (pintype "passive"))
      (node (ref "J100") (pin "1") (pinfunction "1_1") (pintype "passive"))
      (node (ref "J1400") (pin "2") (pinfunction "2_2") (pintype "passive"))
      (node (ref "J1401") (pin "2") (pinfunction "2_2") (pintype "passive"))
      (node (ref "J1402") (pin "2") (pinfunction "2_2") (pintype "passive"))
      (node (ref "J1403") (pin "2") (pinfunction "2_2") (pintype "passive"))
      (node (ref "J1404") (pin "2") (pinfunction "2_2") (pintype "passive"))
      (node (ref "J1405") (pin "2") (pinfunction "2_2") (pintype "passive"))
      (node (ref "J1406") (pin "2") (pinfunction "2_2") (pintype "passive"))
      (node (ref "J1407") (pin "2") (pinfunction "2_2") (pintype "passive"))
      (node (ref "J1408") (pin "2") (pinfunction "2_2") (pintype "passive"))
      (node (ref "J1409") (pin "2") (pinfunction "2_2") (pintype "passive"))
      (node (ref "J200") (pin "1") (pinfunction "1_1") (pintype "passive"))
      (node (ref "J300") (pin "6") (pinfunction "6_6") (pintype "passive"))
      (node (ref "U100") (pin "3") (pinfunction "VDD_3") (pintype "power_in"))
    )
    (net (code "63") (name "5V_ENC") (class "Default")
      (node (ref "C800") (pin "2") (pinfunction "2_2") (pintype "passive"))
      (node (ref "C900") (pin "2") (pinfunction "2_2") (pintype "passive"))
      (node (ref "FB850") (pin "2") (pinfunction "2_2") (pintype "passive"))
      (node (ref "J800") (pin "1") (pinfunction "1_1") (pintype "passive"))
      (node (ref "J900") (pin "1") (pinfunction "1_1") (pintype "passive"))
    )
    (net (code "64") (name "GND") (class "Default")
      (node (ref "C100") (pin "1") (pinfunction "1_1") (pintype "passive"))
      (node (ref "C101") (pin "1") (pinfunction "1_1") (pintype "passive"))
      (node (ref "C1300") (pin "1") (pinfunction "1_1") (pintype "passive"))
      (node (ref "C1301") (pin "1") (pinfunction "1_1") (pintype "passive"))
      (node (ref "C1310") (pin "1") (pinfunction "1_1") (pintype "passive"))
      (node (ref "C1311") (pin "1") (pinfunction "1_1") (pintype "passive"))
      (node (ref "C1320") (pin "1") (pinfunction "1_1") (pintype "passive"))
      (node (ref "C1321") (pin "1") (pinfunction "1_1") (pintype "passive"))
      (node (ref "C1330") (pin "1") (pinfunction "1_1") (pintype "passive"))
      (node (ref "C1331") (pin "1") (pinfunction "1_1") (pintype "passive"))
      (node (ref "C1340") (pin "1") (pinfunction "1_1") (pintype "passive"))
      (node (ref "C1341") (pin "1") (pinfunction "1_1") (pintype "passive"))
      (node (ref "C1350") (pin "1") (pinfunction "1_1") (pintype "passive"))
      (node (ref "C1351") (pin "1") (pinfunction "1_1") (pintype "passive"))
      (node (ref "C1360") (pin "1") (pinfunction "1_1") (pintype "passive"))
      (node (ref "C1361") (pin "1") (pinfunction "1_1") (pintype "passive"))
      (node (ref "C1370") (pin "1") (pinfunction "1_1") (pintype "passive"))
      (node (ref "C1371") (pin "1") (pinfunction "1_1") (pintype "passive"))
      (node (ref "C200") (pin "1") (pinfunction "1_1") (pintype "passive"))
      (node (ref "C300") (pin "1") (pinfunction "1_1") (pintype "passive"))
      (node (ref "C800") (pin "1") (pinfunction "1_1") (pintype "passive"))
      (node (ref "C900") (pin "1") (pinfunction "1_1") (pintype "passive"))
      (node (ref "CN10") (pin "20") (pinfunction "GND_20") (pintype "passive"))
      (node (ref "CN10") (pin "32") (pinfunction "PA4_32") (pintype "passive"))
      (node (ref "CN10") (pin "9") (pinfunction "PF6_9") (pintype "passive"))
      (node (ref "CN7") (pin "19") (pinfunction "GND_19") (pintype "passive"))
      (node (ref "CN7") (pin "20") (pinfunction "GND_20") (pintype "passive"))
      (node (ref "CN7") (pin "22") (pinfunction "GND_22") (pintype "passive"))
      (node (ref "CN7") (pin "8") (pinfunction "GND_8") (pintype "passive"))
      (node (ref "J100") (pin "2") (pinfunction "2_2") (pintype "passive"))
      (node (ref "J1100") (pin "2") (pinfunction "2_2") (pintype "passive"))
      (node (ref "J1300") (pin "2") (pinfunction "2_2") (pintype "passive"))
      (node (ref "J1310") (pin "2") (pinfunction "2_2") (pintype "passive"))
      (node (ref "J1320") (pin "2") (pinfunction "2_2") (pintype "passive"))
      (node (ref "J1330") (pin "2") (pinfunction "2_2") (pintype "passive"))
      (node (ref "J1340") (pin "2") (pinfunction "2_2") (pintype "passive"))
      (node (ref "J1350") (pin "2") (pinfunction "2_2") (pintype "passive"))
      (node (ref "J1360") (pin "2") (pinfunction "2_2") (pintype "passive"))
      (node (ref "J1370") (pin "2") (pinfunction "2_2") (pintype "passive"))
      (node (ref "J1400") (pin "3") (pinfunction "3_3") (pintype "passive"))
      (node (ref "J1401") (pin "3") (pinfunction "3_3") (pintype "passive"))
      (node (ref "J1402") (pin "3") (pinfunction "3_3") (pintype "passive"))
      (node (ref "J1403") (pin "3") (pinfunction "3_3") (pintype "passive"))
      (node (ref "J1404") (pin "3") (pinfunction "3_3") (pintype "passive"))
      (node (ref "J1405") (pin "3") (pinfunction "3_3") (pintype "passive"))
      (node (ref "J1406") (pin "3") (pinfunction "3_3") (pintype "passive"))
      (node (ref "J1407") (pin "3") (pinfunction "3_3") (pintype "passive"))
      (node (ref "J1408") (pin "3") (pinfunction "3_3") (pintype "passive"))
      (node (ref "J1409") (pin "3") (pinfunction "3_3") (pintype "passive"))
      (node (ref "J200") (pin "2") (pinfunction "2_2") (pintype "passive"))
      (node (ref "J300") (pin "1") (pinfunction "1_1") (pintype "passive"))
      (node (ref "J800") (pin "2") (pinfunction "2_2") (pintype "passive"))
      (node (ref "J800") (pin "3") (pinfunction "3_3") (pintype "passive"))
      (node (ref "J900") (pin "2") (pinfunction "2_2") (pintype "passive"))
      (node (ref "J900") (pin "3") (pinfunction "3_3") (pintype "passive"))
      (node (ref "R100") (pin "1") (pinfunction "1_1") (pintype "passive"))
      (node (ref "R101") (pin "2") (pinfunction "2_2") (pintype "passive"))
      (node (ref "U100") (pin "2") (pinfunction "VSS_2") (pintype "power_in"))
      (node (ref "U100") (pin "8") (pinfunction "RS_8") (pintype "input"))
    )
    (net (code "65") (name "Net-(FB1100-Pad2)") (class "Default")
      (node (ref "FB1100") (pin "2") (pinfunction "2_2") (pintype "passive"))
      (node (ref "J1100") (pin "1") (pinfunction "1_1") (pintype "passive"))
    )
    (net (code "66") (name "Net-(J300-Pad2)") (class "Default")
      (node (ref "J300") (pin "2") (pinfunction "2_2") (pintype "passive"))
      (node (ref "R303") (pin "1") (pinfunction "1_1") (pintype "passive"))
    )
    (net (code "67") (name "Net-(J300-Pad3)") (class "Default")
      (node (ref "J300") (pin "3") (pinfunction "3_3") (pintype "passive"))
      (node (ref "R302") (pin "1") (pinfunction "1_1") (pintype "passive"))
    )
    (net (code "68") (name "Net-(J300-Pad4)") (class "Default")
      (node (ref "J300") (pin "4") (pinfunction "4_4") (pintype "passive"))
      (node (ref "R301") (pin "1") (pinfunction "1_1") (pintype "passive"))
    )
    (net (code "69") (name "Net-(J300-Pad5)") (class "Default")
      (node (ref "J300") (pin "5") (pinfunction "5_5") (pintype "passive"))
      (node (ref "R300") (pin "1") (pinfunction "1_1") (pintype "passive"))
    )
    (net (code "70") (name "Net-(J400-Pad2)") (class "Default")
      (node (ref "J400") (pin "2") (pinfunction "2_2") (pintype "passive"))
      (node (ref "R400") (pin "1") (pinfunction "1_1") (pintype "passive"))
    )
    (net (code "71") (name "Net-(J400-Pad3)") (class "Default")
      (node (ref "J400") (pin "3") (pinfunction "3_3") (pintype "passive"))
      (node (ref "R401") (pin "1") (pinfunction "1_1") (pintype "passive"))
    )
    (net (code "72") (name "Net-(J400-Pad4)") (class "Default")
      (node (ref "J400") (pin "4") (pinfunction "4_4") (pintype "passive"))
      (node (ref "R402") (pin "1") (pinfunction "1_1") (pintype "passive"))
    )
    (net (code "73") (name "Net-(J400-Pad5)") (class "Default")
      (node (ref "J400") (pin "5") (pinfunction "5_5") (pintype "passive"))
      (node (ref "R403") (pin "1") (pinfunction "1_1") (pintype "passive"))
    )
    (net (code "74") (name "Net-(J1100-Pad3)") (class "Default")
      (node (ref "J1100") (pin "3") (pinfunction "3_3") (pintype "passive"))
      (node (ref "R1100") (pin "1") (pinfunction "1_1") (pintype "passive"))
    )
    (net (code "75") (name "Net-(J1100-Pad4)") (class "Default")
      (node (ref "J1100") (pin "4") (pinfunction "4_4") (pintype "passive"))
      (node (ref "R1101") (pin "1") (pinfunction "1_1") (pintype "passive"))
    )
    (net (code "76") (name "Net-(J1300-Pad3)") (class "Default")
      (node (ref "J1300") (pin "3") (pinfunction "3_3") (pintype "passive"))
      (node (ref "R1300") (pin "1") (pinfunction "1_1") (pintype "passive"))
    )
    (net (code "77") (name "Net-(J1300-Pad4)") (class "Default")
      (node (ref "J1300") (pin "4") (pinfunction "4_4") (pintype "passive"))
      (node (ref "R1301") (pin "1") (pinfunction "1_1") (pintype "passive"))
    )
    (net (code "78") (name "Net-(J1310-Pad3)") (class "Default")
      (node (ref "J1310") (pin "3") (pinfunction "3_3") (pintype "passive"))
      (node (ref "R1310") (pin "1") (pinfunction "1_1") (pintype "passive"))
    )
    (net (code "79") (name "Net-(J1310-Pad4)") (class "Default")
      (node (ref "J1310") (pin "4") (pinfunction "4_4") (pintype "passive"))
      (node (ref "R1311") (pin "1") (pinfunction "1_1") (pintype "passive"))
    )
    (net (code "80") (name "Net-(J1320-Pad3)") (class "Default")
      (node (ref "J1320") (pin "3") (pinfunction "3_3") (pintype "passive"))
      (node (ref "R1320") (pin "1") (pinfunction "1_1") (pintype "passive"))
    )
    (net (code "81") (name "Net-(J1320-Pad4)") (class "Default")
      (node (ref "J1320") (pin "4") (pinfunction "4_4") (pintype "passive"))
      (node (ref "R1321") (pin "1") (pinfunction "1_1") (pintype "passive"))
    )
    (net (code "82") (name "Net-(J1330-Pad3)") (class "Default")
      (node (ref "J1330") (pin "3") (pinfunction "3_3") (pintype "passive"))
      (node (ref "R1330") (pin "1") (pinfunction "1_1") (pintype "passive"))
    )
    (net (code "83") (name "Net-(J1330-Pad4)") (class "Default")
      (node (ref "J1330") (pin "4") (pinfunction "4_4") (pintype "passive"))
      (node (ref "R1331") (pin "1") (pinfunction "1_1") (pintype "passive"))
    )
    (net (code "84") (name "Net-(J1340-Pad3)") (class "Default")
      (node (ref "J1340") (pin "3") (pinfunction "3_3") (pintype "passive"))
      (node (ref "R1340") (pin "1") (pinfunction "1_1") (pintype "passive"))
    )
    (net (code "85") (name "Net-(J1340-Pad4)") (class "Default")
      (node (ref "J1340") (pin "4") (pinfunction "4_4") (pintype "passive"))
      (node (ref "R1341") (pin "1") (pinfunction "1_1") (pintype "passive"))
    )
    (net (code "86") (name "Net-(J1350-Pad3)") (class "Default")
      (node (ref "J1350") (pin "3") (pinfunction "3_3") (pintype "passive"))
      (node (ref "R1350") (pin "1") (pinfunction "1_1") (pintype "passive"))
    )
    (net (code "87") (name "Net-(J1350-Pad4)") (class "Default")
      (node (ref "J1350") (pin "4") (pinfunction "4_4") (pintype "passive"))
      (node (ref "R1351") (pin "1") (pinfunction "1_1") (pintype "passive"))
    )
    (net (code "88") (name "Net-(J1360-Pad3)") (class "Default")
      (node (ref "J1360") (pin "3") (pinfunction "3_3") (pintype "passive"))
      (node (ref "R1360") (pin "1") (pinfunction "1_1") (pintype "passive"))
    )
    (net (code "89") (name "Net-(J1360-Pad4)") (class "Default")
      (node (ref "J1360") (pin "4") (pinfunction "4_4") (pintype "passive"))
      (node (ref "R1361") (pin "1") (pinfunction "1_1") (pintype "passive"))
    )
    (net (code "90") (name "Net-(J1370-Pad3)") (class "Default")
      (node (ref "J1370") (pin "3") (pinfunction "3_3") (pintype "passive"))
      (node (ref "R1370") (pin "1") (pinfunction "1_1") (pintype "passive"))
    )
    (net (code "91") (name "Net-(J1370-Pad4)") (class "Default")
      (node (ref "J1370") (pin "4") (pinfunction "4_4") (pintype "passive"))
      (node (ref "R1371") (pin "1") (pinfunction "1_1") (pintype "passive"))
    )
    (net (code "92") (name "Net-(J1400-Pad1)") (class "Default")
      (node (ref "J1400") (pin "1") (pinfunction "1_1") (pintype "passive"))
      (node (ref "R1400") (pin "2") (pinfunction "2_2") (pintype "passive"))
    )
    (net (code "93") (name "Net-(J1401-Pad1)") (class "Default")
      (node (ref "J1401") (pin "1") (pinfunction "1_1") (pintype "passive"))
      (node (ref "R1401") (pin "2") (pinfunction "2_2") (pintype "passive"))
    )
    (net (code "94") (name "Net-(J1402-Pad1)") (class "Default")
      (node (ref "J1402") (pin "1") (pinfunction "1_1") (pintype "passive"))
      (node (ref "R1402") (pin "2") (pinfunction "2_2") (pintype "passive"))
    )
    (net (code "95") (name "Net-(J1403-Pad1)") (class "Default")
      (node (ref "J1403") (pin "1") (pinfunction "1_1") (pintype "passive"))
      (node (ref "R1403") (pin "2") (pinfunction "2_2") (pintype "passive"))
    )
    (net (code "96") (name "Net-(J1404-Pad1)") (class "Default")
      (node (ref "J1404") (pin "1") (pinfunction "1_1") (pintype "passive"))
      (node (ref "R1404") (pin "2") (pinfunction "2_2") (pintype "passive"))
    )
    (net (code "97") (name "Net-(J1405-Pad1)") (class "Default")
      (node (ref "J1405") (pin "1") (pinfunction "1_1") (pintype "passive"))
      (node (ref "R1405") (pin "2") (pinfunction "2_2") (pintype "passive"))
    )
    (net (code "98") (name "Net-(J1406-Pad1)") (class "Default")
      (node (ref "J1406") (pin "1") (pinfunction "1_1") (pintype "passive"))
      (node (ref "R1406") (pin "2") (pinfunction "2_2") (pintype "passive"))
    )
    (net (code "99") (name "Net-(J1407-Pad1)") (class "Default")
      (node (ref "J1407") (pin "1") (pinfunction "1_1") (pintype "passive"))
      (node (ref "R1407") (pin "2") (pinfunction "2_2") (pintype "passive"))
    )
    (net (code "100") (name "Net-(J1408-Pad1)") (class "Default")
      (node (ref "J1408") (pin "1") (pinfunction "1_1") (pintype "passive"))
      (node (ref "R1408") (pin "2") (pinfunction "2_2") (pintype "passive"))
    )
    (net (code "101") (name "Net-(J1409-Pad1)") (class "Default")
      (node (ref "J1409") (pin "1") (pinfunction "1_1") (pintype "passive"))
      (node (ref "R1409") (pin "2") (pinfunction "2_2") (pintype "passive"))
    )
    (net (code "102") (name "Net-(U100-RXD)") (class "Default")
      (node (ref "R104") (pin "1") (pinfunction "1_1") (pintype "passive"))
      (node (ref "U100") (pin "4") (pinfunction "RXD_4") (pintype "output"))
    )
    (net (code "103") (name "Net-(U100-TXD)") (class "Default")
      (node (ref "R103") (pin "1") (pinfunction "1_1") (pintype "passive"))
      (node (ref "U100") (pin "1") (pinfunction "TXD_1") (pintype "input"))
    )
    (net (code "104") (name "unconnected-(CN7-+3V3-Pad12)") (class "Default")
      (node (ref "CN7") (pin "12") (pinfunction "+3V3_12") (pintype "passive"))
    )
    (net (code "105") (name "unconnected-(CN7-+3V3-Pad16)") (class "Default")
      (node (ref "CN7") (pin "16") (pinfunction "+3V3_16") (pintype "passive"))
    )
    (net (code "106") (name "unconnected-(CN7-+5V-Pad18)") (class "Default")
      (node (ref "CN7") (pin "18") (pinfunction "+5V_18") (pintype "passive"))
    )
    (net (code "107") (name "unconnected-(CN7-BOOT0-Pad7)") (class "Default")
      (node (ref "CN7") (pin "7") (pinfunction "BOOT0_7") (pintype "passive"))
    )
    (net (code "108") (name "unconnected-(CN7-E5V-Pad6)") (class "Default")
      (node (ref "CN7") (pin "6") (pinfunction "E5V_6") (pintype "passive"))
    )
    (net (code "109") (name "unconnected-(CN7-NRST-Pad14)") (class "Default")
      (node (ref "CN7") (pin "14") (pinfunction "NRST_14") (pintype "passive"))
    )
    (net (code "110") (name "unconnected-(CN7-PA0-Pad28)") (class "Default")
      (node (ref "CN7") (pin "28") (pinfunction "PA0_28") (pintype "passive"))
    )
    (net (code "111") (name "unconnected-(CN7-Pad10)") (class "Default")
      (node (ref "CN7") (pin "10") (pintype "passive"))
    )
    (net (code "112") (name "unconnected-(CN7-Pad26)") (class "Default")
      (node (ref "CN7") (pin "26") (pintype "passive"))
    )
    (net (code "113") (name "unconnected-(CN7-VBAT-Pad33)") (class "Default")
      (node (ref "CN7") (pin "33") (pinfunction "VBAT_33") (pintype "passive"))
    )
    (net (code "114") (name "unconnected-(CN7-VIN-Pad24)") (class "Default")
      (node (ref "CN7") (pin "24") (pinfunction "VIN_24") (pintype "passive"))
    )
    (net (code "115") (name "unconnected-(CN10-+3V3-Pad16)") (class "Default")
      (node (ref "CN10") (pin "16") (pinfunction "+3V3_16") (pintype "passive"))
    )
    (net (code "116") (name "unconnected-(CN10-BOOT0-Pad7)") (class "Default")
      (node (ref "CN10") (pin "7") (pinfunction "BOOT0_7") (pintype "passive"))
    )
    (net (code "117") (name "unconnected-(J400-Pad1)") (class "Default")
      (node (ref "J400") (pin "1") (pinfunction "1_1") (pintype "passive"))
    )
    (net (code "118") (name "unconnected-(J400-Pad6)") (class "Default")
      (node (ref "J400") (pin "6") (pinfunction "6_6") (pintype "passive"))
    )
    (net (code "119") (name "unconnected-(J800-Pad5)") (class "Default")
      (node (ref "J800") (pin "5") (pinfunction "5_5") (pintype "passive"))
    )
    (net (code "120") (name "unconnected-(J900-Pad5)") (class "Default")
      (node (ref "J900") (pin "5") (pinfunction "5_5") (pintype "passive"))
    )
    (net (code "121") (name "unconnected-(U100-VREF-Pad5)") (class "Default")
      (node (ref "U100") (pin "5") (pinfunction "VREF_5") (pintype "output"))
    )
  )
)
